# STM321.net
KiCad netlist of a schematic drawn in Altium Designer
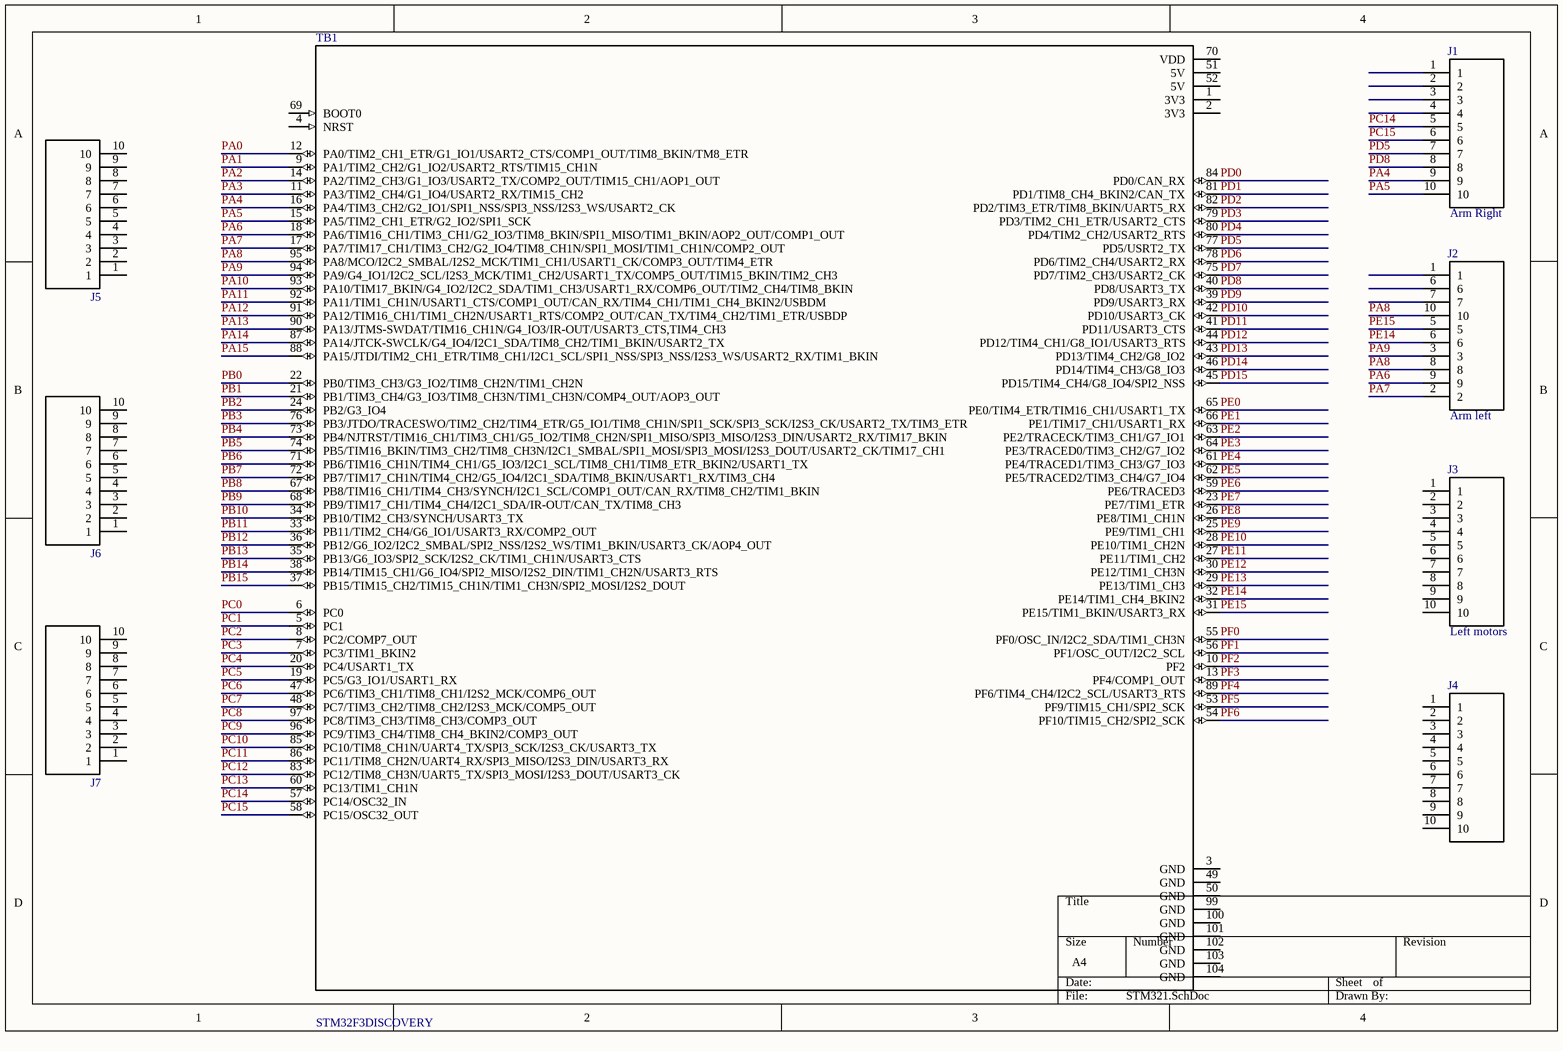
[diagram p0: STM321.SchDoc]

(export (version "E")
  (design (tool "Eeschema 10.0.6"))
  (components
    (comp (ref "J1")
      (value "2-1761603-3")
      (footprint "*TE_2-1761603-3")
      (description "Header, Pin, Idc, Amp-Latch, 10 Pos, Low Profile, Pcb, Vertical, Blue")
      (fields (field (name "MF") "TE Connectivity"))
      (libsource (lib "2-1761603-3") (part "2-1761603-3"))
    )
    (comp (ref "J2")
      (value "2-1761603-3")
      (footprint "*TE_2-1761603-3")
      (description "Header, Pin, Idc, Amp-Latch, 10 Pos, Low Profile, Pcb, Vertical, Blue")
      (fields (field (name "MF") "TE Connectivity"))
      (libsource (lib "") (part "2-1761603-3_1"))
    )
    (comp (ref "J3")
      (value "2-1761603-3")
      (footprint "*TE_2-1761603-3")
      (description "Header, Pin, Idc, Amp-Latch, 10 Pos, Low Profile, Pcb, Vertical, Blue")
      (fields (field (name "MF") "TE Connectivity"))
      (libsource (lib "2-1761603-3") (part "2-1761603-3"))
    )
    (comp (ref "J4")
      (value "2-1761603-3")
      (footprint "*TE_2-1761603-3")
      (description "Header, Pin, Idc, Amp-Latch, 10 Pos, Low Profile, Pcb, Vertical, Blue")
      (fields (field (name "MF") "TE Connectivity"))
      (libsource (lib "2-1761603-3") (part "2-1761603-3"))
    )
    (comp (ref "J5")
      (value "2-1761603-3")
      (footprint "*TE_2-1761603-3")
      (description "Header, Pin, Idc, Amp-Latch, 10 Pos, Low Profile, Pcb, Vertical, Blue")
      (fields (field (name "MF") "TE Connectivity"))
      (libsource (lib "2-1761603-3") (part "2-1761603-3"))
    )
    (comp (ref "J6")
      (value "2-1761603-3")
      (footprint "*TE_2-1761603-3")
      (description "Header, Pin, Idc, Amp-Latch, 10 Pos, Low Profile, Pcb, Vertical, Blue")
      (fields (field (name "MF") "TE Connectivity"))
      (libsource (lib "2-1761603-3") (part "2-1761603-3"))
    )
    (comp (ref "J7")
      (value "2-1761603-3")
      (footprint "*TE_2-1761603-3")
      (description "Header, Pin, Idc, Amp-Latch, 10 Pos, Low Profile, Pcb, Vertical, Blue")
      (fields (field (name "MF") "TE Connectivity"))
      (libsource (lib "2-1761603-3") (part "2-1761603-3"))
    )
    (comp (ref "TB1")
      (value "STM32F3DISCOVERY")
      (footprint "*SHIELD_STM32F3DISCOVERY")
      (description "STM32F303VCT6 Discovery STM32F3 ARMÂ® CortexÂ®-M4 MCU 32-Bit Embedded Evaluation Board")
      (fields (field (name "MF") "STMicroelectronics"))
      (libsource (lib "STM32F3DISCOVERY") (part "STM32F3DISCOVERY"))
    )
  )
  (nets
    (net (code "1") (name "/PA0") (class "Default")
      (node (ref "TB1") (pin "12") (pinfunction "PA0/TIM2_CH1_ETR/G1_IO1/USART2_CTS/COMP1_OUT/TIM8_BKIN/TM8_ETR_12") (pintype "bidirectional"))
    )
    (net (code "2") (name "/PA1") (class "Default")
      (node (ref "TB1") (pin "9") (pinfunction "PA1/TIM2_CH2/G1_IO2/USART2_RTS/TIM15_CH1N_9") (pintype "bidirectional"))
    )
    (net (code "3") (name "/PA2") (class "Default")
      (node (ref "TB1") (pin "14") (pinfunction "PA2/TIM2_CH3/G1_IO3/USART2_TX/COMP2_OUT/TIM15_CH1/AOP1_OUT_14") (pintype "bidirectional"))
    )
    (net (code "4") (name "/PA3") (class "Default")
      (node (ref "TB1") (pin "11") (pinfunction "PA3/TIM2_CH4/G1_IO4/USART2_RX/TIM15_CH2_11") (pintype "bidirectional"))
    )
    (net (code "5") (name "/PA4") (class "Default")
      (node (ref "J1") (pin "9") (pinfunction "9_9") (pintype "passive"))
      (node (ref "TB1") (pin "16") (pinfunction "PA4/TIM3_CH2/G2_IO1/SPI1_NSS/SPI3_NSS/I2S3_WS/USART2_CK_16") (pintype "bidirectional"))
    )
    (net (code "6") (name "/PA5") (class "Default")
      (node (ref "J1") (pin "10") (pinfunction "10_10") (pintype "passive"))
      (node (ref "TB1") (pin "15") (pinfunction "PA5/TIM2_CH1_ETR/G2_IO2/SPI1_SCK_15") (pintype "bidirectional"))
    )
    (net (code "7") (name "/PA6") (class "Default")
      (node (ref "J2") (pin "9") (pinfunction "9_9") (pintype "passive"))
      (node (ref "TB1") (pin "18") (pinfunction "PA6/TIM16_CH1/TIM3_CH1/G2_IO3/TIM8_BKIN/SPI1_MISO/TIM1_BKIN/AOP2_OUT/COMP1_OUT_18") (pintype "bidirectional"))
    )
    (net (code "8") (name "/PA7") (class "Default")
      (node (ref "J2") (pin "2") (pinfunction "2_2") (pintype "passive"))
      (node (ref "TB1") (pin "17") (pinfunction "PA7/TIM17_CH1/TIM3_CH2/G2_IO4/TIM8_CH1N/SPI1_MOSI/TIM1_CH1N/COMP2_OUT_17") (pintype "bidirectional"))
    )
    (net (code "9") (name "/PA8") (class "Default")
      (node (ref "J2") (pin "10") (pinfunction "10_10") (pintype "passive"))
      (node (ref "J2") (pin "8") (pinfunction "8_8") (pintype "passive"))
      (node (ref "TB1") (pin "95") (pinfunction "PA8/MCO/I2C2_SMBAL/I2S2_MCK/TIM1_CH1/USART1_CK/COMP3_OUT/TIM4_ETR_95") (pintype "bidirectional"))
    )
    (net (code "10") (name "/PA9") (class "Default")
      (node (ref "J2") (pin "3") (pinfunction "3_3") (pintype "passive"))
      (node (ref "TB1") (pin "94") (pinfunction "PA9/G4_IO1/I2C2_SCL/I2S3_MCK/TIM1_CH2/USART1_TX/COMP5_OUT/TIM15_BKIN/TIM2_CH3_94") (pintype "bidirectional"))
    )
    (net (code "11") (name "/PA10") (class "Default")
      (node (ref "TB1") (pin "93") (pinfunction "PA10/TIM17_BKIN/G4_IO2/I2C2_SDA/TIM1_CH3/USART1_RX/COMP6_OUT/TIM2_CH4/TIM8_BKIN_93") (pintype "bidirectional"))
    )
    (net (code "12") (name "/PA11") (class "Default")
      (node (ref "TB1") (pin "92") (pinfunction "PA11/TIM1_CH1N/USART1_CTS/COMP1_OUT/CAN_RX/TIM4_CH1/TIM1_CH4_BKIN2/USBDM_92") (pintype "bidirectional"))
    )
    (net (code "13") (name "/PA12") (class "Default")
      (node (ref "TB1") (pin "91") (pinfunction "PA12/TIM16_CH1/TIM1_CH2N/USART1_RTS/COMP2_OUT/CAN_TX/TIM4_CH2/TIM1_ETR/USBDP_91") (pintype "bidirectional"))
    )
    (net (code "14") (name "/PA13") (class "Default")
      (node (ref "TB1") (pin "90") (pinfunction "PA13/JTMS-SWDAT/TIM16_CH1N/G4_IO3/IR-OUT/USART3_CTS,TIM4_CH3_90") (pintype "bidirectional"))
    )
    (net (code "15") (name "/PA14") (class "Default")
      (node (ref "TB1") (pin "87") (pinfunction "PA14/JTCK-SWCLK/G4_IO4/I2C1_SDA/TIM8_CH2/TIM1_BKIN/USART2_TX_87") (pintype "bidirectional"))
    )
    (net (code "16") (name "/PA15") (class "Default")
      (node (ref "TB1") (pin "88") (pinfunction "PA15/JTDI/TIM2_CH1_ETR/TIM8_CH1/I2C1_SCL/SPI1_NSS/SPI3_NSS/I2S3_WS/USART2_RX/TIM1_BKIN_88") (pintype "bidirectional"))
    )
    (net (code "17") (name "/PB0") (class "Default")
      (node (ref "TB1") (pin "22") (pinfunction "PB0/TIM3_CH3/G3_IO2/TIM8_CH2N/TIM1_CH2N_22") (pintype "bidirectional"))
    )
    (net (code "18") (name "/PB1") (class "Default")
      (node (ref "TB1") (pin "21") (pinfunction "PB1/TIM3_CH4/G3_IO3/TIM8_CH3N/TIM1_CH3N/COMP4_OUT/AOP3_OUT_21") (pintype "bidirectional"))
    )
    (net (code "19") (name "/PB2") (class "Default")
      (node (ref "TB1") (pin "24") (pinfunction "PB2/G3_IO4_24") (pintype "bidirectional"))
    )
    (net (code "20") (name "/PB3") (class "Default")
      (node (ref "TB1") (pin "76") (pinfunction "PB3/JTDO/TRACESWO/TIM2_CH2/TIM4_ETR/G5_IO1/TIM8_CH1N/SPI1_SCK/SPI3_SCK/I2S3_CK/USART2_TX/TIM3_ETR_76") (pintype "bidirectional"))
    )
    (net (code "21") (name "/PB4") (class "Default")
      (node (ref "TB1") (pin "73") (pinfunction "PB4/NJTRST/TIM16_CH1/TIM3_CH1/G5_IO2/TIM8_CH2N/SPI1_MISO/SPI3_MISO/I2S3_DIN/USART2_RX/TIM17_BKIN_73") (pintype "bidirectional"))
    )
    (net (code "22") (name "/PB5") (class "Default")
      (node (ref "TB1") (pin "74") (pinfunction "PB5/TIM16_BKIN/TIM3_CH2/TIM8_CH3N/I2C1_SMBAL/SPI1_MOSI/SPI3_MOSI/I2S3_DOUT/USART2_CK/TIM17_CH1_74") (pintype "bidirectional"))
    )
    (net (code "23") (name "/PB6") (class "Default")
      (node (ref "TB1") (pin "71") (pinfunction "PB6/TIM16_CH1N/TIM4_CH1/G5_IO3/I2C1_SCL/TIM8_CH1/TIM8_ETR_BKIN2/USART1_TX_71") (pintype "bidirectional"))
    )
    (net (code "24") (name "/PB7") (class "Default")
      (node (ref "TB1") (pin "72") (pinfunction "PB7/TIM17_CH1N/TIM4_CH2/G5_IO4/I2C1_SDA/TIM8_BKIN/USART1_RX/TIM3_CH4_72") (pintype "bidirectional"))
    )
    (net (code "25") (name "/PB8") (class "Default")
      (node (ref "TB1") (pin "67") (pinfunction "PB8/TIM16_CH1/TIM4_CH3/SYNCH/I2C1_SCL/COMP1_OUT/CAN_RX/TIM8_CH2/TIM1_BKIN_67") (pintype "bidirectional"))
    )
    (net (code "26") (name "/PB9") (class "Default")
      (node (ref "TB1") (pin "68") (pinfunction "PB9/TIM17_CH1/TIM4_CH4/I2C1_SDA/IR-OUT/CAN_TX/TIM8_CH3_68") (pintype "bidirectional"))
    )
    (net (code "27") (name "/PB10") (class "Default")
      (node (ref "TB1") (pin "34") (pinfunction "PB10/TIM2_CH3/SYNCH/USART3_TX_34") (pintype "bidirectional"))
    )
    (net (code "28") (name "/PB11") (class "Default")
      (node (ref "TB1") (pin "33") (pinfunction "PB11/TIM2_CH4/G6_IO1/USART3_RX/COMP2_OUT_33") (pintype "bidirectional"))
    )
    (net (code "29") (name "/PB12") (class "Default")
      (node (ref "TB1") (pin "36") (pinfunction "PB12/G6_IO2/I2C2_SMBAL/SPI2_NSS/I2S2_WS/TIM1_BKIN/USART3_CK/AOP4_OUT_36") (pintype "bidirectional"))
    )
    (net (code "30") (name "/PB13") (class "Default")
      (node (ref "TB1") (pin "35") (pinfunction "PB13/G6_IO3/SPI2_SCK/I2S2_CK/TIM1_CH1N/USART3_CTS_35") (pintype "bidirectional"))
    )
    (net (code "31") (name "/PB14") (class "Default")
      (node (ref "TB1") (pin "38") (pinfunction "PB14/TIM15_CH1/G6_IO4/SPI2_MISO/I2S2_DIN/TIM1_CH2N/USART3_RTS_38") (pintype "bidirectional"))
    )
    (net (code "32") (name "/PB15") (class "Default")
      (node (ref "TB1") (pin "37") (pinfunction "PB15/TIM15_CH2/TIM15_CH1N/TIM1_CH3N/SPI2_MOSI/I2S2_DOUT_37") (pintype "bidirectional"))
    )
    (net (code "33") (name "/PC0") (class "Default")
      (node (ref "TB1") (pin "6") (pinfunction "PC0_6") (pintype "bidirectional"))
    )
    (net (code "34") (name "/PC1") (class "Default")
      (node (ref "TB1") (pin "5") (pinfunction "PC1_5") (pintype "bidirectional"))
    )
    (net (code "35") (name "/PC2") (class "Default")
      (node (ref "TB1") (pin "8") (pinfunction "PC2/COMP7_OUT_8") (pintype "bidirectional"))
    )
    (net (code "36") (name "/PC3") (class "Default")
      (node (ref "TB1") (pin "7") (pinfunction "PC3/TIM1_BKIN2_7") (pintype "bidirectional"))
    )
    (net (code "37") (name "/PC4") (class "Default")
      (node (ref "TB1") (pin "20") (pinfunction "PC4/USART1_TX_20") (pintype "bidirectional"))
    )
    (net (code "38") (name "/PC5") (class "Default")
      (node (ref "TB1") (pin "19") (pinfunction "PC5/G3_IO1/USART1_RX_19") (pintype "bidirectional"))
    )
    (net (code "39") (name "/PC6") (class "Default")
      (node (ref "TB1") (pin "47") (pinfunction "PC6/TIM3_CH1/TIM8_CH1/I2S2_MCK/COMP6_OUT_47") (pintype "bidirectional"))
    )
    (net (code "40") (name "/PC7") (class "Default")
      (node (ref "TB1") (pin "48") (pinfunction "PC7/TIM3_CH2/TIM8_CH2/I2S3_MCK/COMP5_OUT_48") (pintype "bidirectional"))
    )
    (net (code "41") (name "/PC8") (class "Default")
      (node (ref "TB1") (pin "97") (pinfunction "PC8/TIM3_CH3/TIM8_CH3/COMP3_OUT_97") (pintype "bidirectional"))
    )
    (net (code "42") (name "/PC9") (class "Default")
      (node (ref "TB1") (pin "96") (pinfunction "PC9/TIM3_CH4/TIM8_CH4_BKIN2/COMP3_OUT_96") (pintype "bidirectional"))
    )
    (net (code "43") (name "/PC10") (class "Default")
      (node (ref "TB1") (pin "85") (pinfunction "PC10/TIM8_CH1N/UART4_TX/SPI3_SCK/I2S3_CK/USART3_TX_85") (pintype "bidirectional"))
    )
    (net (code "44") (name "/PC11") (class "Default")
      (node (ref "TB1") (pin "86") (pinfunction "PC11/TIM8_CH2N/UART4_RX/SPI3_MISO/I2S3_DIN/USART3_RX_86") (pintype "bidirectional"))
    )
    (net (code "45") (name "/PC12") (class "Default")
      (node (ref "TB1") (pin "83") (pinfunction "PC12/TIM8_CH3N/UART5_TX/SPI3_MOSI/I2S3_DOUT/USART3_CK_83") (pintype "bidirectional"))
    )
    (net (code "46") (name "/PC13") (class "Default")
      (node (ref "TB1") (pin "60") (pinfunction "PC13/TIM1_CH1N_60") (pintype "bidirectional"))
    )
    (net (code "47") (name "/PC14") (class "Default")
      (node (ref "J1") (pin "5") (pinfunction "5_5") (pintype "passive"))
      (node (ref "TB1") (pin "57") (pinfunction "PC14/OSC32_IN_57") (pintype "bidirectional"))
    )
    (net (code "48") (name "/PC15") (class "Default")
      (node (ref "J1") (pin "6") (pinfunction "6_6") (pintype "passive"))
      (node (ref "TB1") (pin "58") (pinfunction "PC15/OSC32_OUT_58") (pintype "bidirectional"))
    )
    (net (code "49") (name "/PD0") (class "Default")
      (node (ref "TB1") (pin "84") (pinfunction "PD0/CAN_RX_84") (pintype "bidirectional"))
    )
    (net (code "50") (name "/PD1") (class "Default")
      (node (ref "TB1") (pin "81") (pinfunction "PD1/TIM8_CH4_BKIN2/CAN_TX_81") (pintype "bidirectional"))
    )
    (net (code "51") (name "/PD2") (class "Default")
      (node (ref "TB1") (pin "82") (pinfunction "PD2/TIM3_ETR/TIM8_BKIN/UART5_RX_82") (pintype "bidirectional"))
    )
    (net (code "52") (name "/PD3") (class "Default")
      (node (ref "TB1") (pin "79") (pinfunction "PD3/TIM2_CH1_ETR/USART2_CTS_79") (pintype "bidirectional"))
    )
    (net (code "53") (name "/PD4") (class "Default")
      (node (ref "TB1") (pin "80") (pinfunction "PD4/TIM2_CH2/USART2_RTS_80") (pintype "bidirectional"))
    )
    (net (code "54") (name "/PD5") (class "Default")
      (node (ref "J1") (pin "7") (pinfunction "7_7") (pintype "passive"))
      (node (ref "TB1") (pin "77") (pinfunction "PD5/USRT2_TX_77") (pintype "bidirectional"))
    )
    (net (code "55") (name "/PD6") (class "Default")
      (node (ref "TB1") (pin "78") (pinfunction "PD6/TIM2_CH4/USART2_RX_78") (pintype "bidirectional"))
    )
    (net (code "56") (name "/PD7") (class "Default")
      (node (ref "TB1") (pin "75") (pinfunction "PD7/TIM2_CH3/USART2_CK_75") (pintype "bidirectional"))
    )
    (net (code "57") (name "/PD8") (class "Default")
      (node (ref "J1") (pin "8") (pinfunction "8_8") (pintype "passive"))
      (node (ref "TB1") (pin "40") (pinfunction "PD8/USART3_TX_40") (pintype "bidirectional"))
    )
    (net (code "58") (name "/PD9") (class "Default")
      (node (ref "TB1") (pin "39") (pinfunction "PD9/USART3_RX_39") (pintype "bidirectional"))
    )
    (net (code "59") (name "/PD10") (class "Default")
      (node (ref "TB1") (pin "42") (pinfunction "PD10/USART3_CK_42") (pintype "bidirectional"))
    )
    (net (code "60") (name "/PD11") (class "Default")
      (node (ref "TB1") (pin "41") (pinfunction "PD11/USART3_CTS_41") (pintype "bidirectional"))
    )
    (net (code "61") (name "/PD12") (class "Default")
      (node (ref "TB1") (pin "44") (pinfunction "PD12/TIM4_CH1/G8_IO1/USART3_RTS_44") (pintype "bidirectional"))
    )
    (net (code "62") (name "/PD13") (class "Default")
      (node (ref "TB1") (pin "43") (pinfunction "PD13/TIM4_CH2/G8_IO2_43") (pintype "bidirectional"))
    )
    (net (code "63") (name "/PD14") (class "Default")
      (node (ref "TB1") (pin "46") (pinfunction "PD14/TIM4_CH3/G8_IO3_46") (pintype "bidirectional"))
    )
    (net (code "64") (name "/PD15") (class "Default")
      (node (ref "TB1") (pin "45") (pinfunction "PD15/TIM4_CH4/G8_IO4/SPI2_NSS_45") (pintype "bidirectional"))
    )
    (net (code "65") (name "/PE0") (class "Default")
      (node (ref "TB1") (pin "65") (pinfunction "PE0/TIM4_ETR/TIM16_CH1/USART1_TX_65") (pintype "bidirectional"))
    )
    (net (code "66") (name "/PE1") (class "Default")
      (node (ref "TB1") (pin "66") (pinfunction "PE1/TIM17_CH1/USART1_RX_66") (pintype "bidirectional"))
    )
    (net (code "67") (name "/PE2") (class "Default")
      (node (ref "TB1") (pin "63") (pinfunction "PE2/TRACECK/TIM3_CH1/G7_IO1_63") (pintype "bidirectional"))
    )
    (net (code "68") (name "/PE3") (class "Default")
      (node (ref "TB1") (pin "64") (pinfunction "PE3/TRACED0/TIM3_CH2/G7_IO2_64") (pintype "bidirectional"))
    )
    (net (code "69") (name "/PE4") (class "Default")
      (node (ref "TB1") (pin "61") (pinfunction "PE4/TRACED1/TIM3_CH3/G7_IO3_61") (pintype "bidirectional"))
    )
    (net (code "70") (name "/PE5") (class "Default")
      (node (ref "TB1") (pin "62") (pinfunction "PE5/TRACED2/TIM3_CH4/G7_IO4_62") (pintype "bidirectional"))
    )
    (net (code "71") (name "/PE6") (class "Default")
      (node (ref "TB1") (pin "59") (pinfunction "PE6/TRACED3_59") (pintype "bidirectional"))
    )
    (net (code "72") (name "/PE7") (class "Default")
      (node (ref "TB1") (pin "23") (pinfunction "PE7/TIM1_ETR_23") (pintype "bidirectional"))
    )
    (net (code "73") (name "/PE8") (class "Default")
      (node (ref "TB1") (pin "26") (pinfunction "PE8/TIM1_CH1N_26") (pintype "bidirectional"))
    )
    (net (code "74") (name "/PE9") (class "Default")
      (node (ref "TB1") (pin "25") (pinfunction "PE9/TIM1_CH1_25") (pintype "bidirectional"))
    )
    (net (code "75") (name "/PE10") (class "Default")
      (node (ref "TB1") (pin "28") (pinfunction "PE10/TIM1_CH2N_28") (pintype "bidirectional"))
    )
    (net (code "76") (name "/PE11") (class "Default")
      (node (ref "TB1") (pin "27") (pinfunction "PE11/TIM1_CH2_27") (pintype "bidirectional"))
    )
    (net (code "77") (name "/PE12") (class "Default")
      (node (ref "TB1") (pin "30") (pinfunction "PE12/TIM1_CH3N_30") (pintype "bidirectional"))
    )
    (net (code "78") (name "/PE13") (class "Default")
      (node (ref "TB1") (pin "29") (pinfunction "PE13/TIM1_CH3_29") (pintype "bidirectional"))
    )
    (net (code "79") (name "/PE14") (class "Default")
      (node (ref "J2") (pin "6") (pinfunction "6_6") (pintype "passive"))
      (node (ref "TB1") (pin "32") (pinfunction "PE14/TIM1_CH4_BKIN2_32") (pintype "bidirectional"))
    )
    (net (code "80") (name "/PE15") (class "Default")
      (node (ref "J2") (pin "5") (pinfunction "5_5") (pintype "passive"))
      (node (ref "TB1") (pin "31") (pinfunction "PE15/TIM1_BKIN/USART3_RX_31") (pintype "bidirectional"))
    )
    (net (code "81") (name "/PF0") (class "Default")
      (node (ref "TB1") (pin "55") (pinfunction "PF0/OSC_IN/I2C2_SDA/TIM1_CH3N_55") (pintype "bidirectional"))
    )
    (net (code "82") (name "/PF1") (class "Default")
      (node (ref "TB1") (pin "56") (pinfunction "PF1/OSC_OUT/I2C2_SCL_56") (pintype "bidirectional"))
    )
    (net (code "83") (name "/PF2") (class "Default")
      (node (ref "TB1") (pin "10") (pinfunction "PF2_10") (pintype "bidirectional"))
    )
    (net (code "84") (name "/PF3") (class "Default")
      (node (ref "TB1") (pin "13") (pinfunction "PF4/COMP1_OUT_13") (pintype "bidirectional"))
    )
    (net (code "85") (name "/PF4") (class "Default")
      (node (ref "TB1") (pin "89") (pinfunction "PF6/TIM4_CH4/I2C2_SCL/USART3_RTS_89") (pintype "bidirectional"))
    )
    (net (code "86") (name "/PF5") (class "Default")
      (node (ref "TB1") (pin "53") (pinfunction "PF9/TIM15_CH1/SPI2_SCK_53") (pintype "bidirectional"))
    )
    (net (code "87") (name "/PF6") (class "Default")
      (node (ref "TB1") (pin "54") (pinfunction "PF10/TIM15_CH2/SPI2_SCK_54") (pintype "bidirectional"))
    )
    (net (code "88") (name "unconnected-(J1-Pad1)") (class "Default")
      (node (ref "J1") (pin "1") (pinfunction "1_1") (pintype "passive"))
    )
    (net (code "89") (name "unconnected-(J1-Pad2)") (class "Default")
      (node (ref "J1") (pin "2") (pinfunction "2_2") (pintype "passive"))
    )
    (net (code "90") (name "unconnected-(J1-Pad3)") (class "Default")
      (node (ref "J1") (pin "3") (pinfunction "3_3") (pintype "passive"))
    )
    (net (code "91") (name "unconnected-(J1-Pad4)") (class "Default")
      (node (ref "J1") (pin "4") (pinfunction "4_4") (pintype "passive"))
    )
    (net (code "92") (name "unconnected-(J2-Pad1)") (class "Default")
      (node (ref "J2") (pin "1") (pinfunction "1_1") (pintype "passive"))
    )
    (net (code "93") (name "unconnected-(J2-Pad6)") (class "Default")
      (node (ref "J2") (pin "6") (pinfunction "6_6") (pintype "passive"))
    )
    (net (code "94") (name "unconnected-(J2-Pad7)") (class "Default")
      (node (ref "J2") (pin "7") (pinfunction "7_7") (pintype "passive"))
    )
    (net (code "95") (name "unconnected-(J3-Pad1)") (class "Default")
      (node (ref "J3") (pin "1") (pinfunction "1_1") (pintype "passive"))
    )
    (net (code "96") (name "unconnected-(J3-Pad2)") (class "Default")
      (node (ref "J3") (pin "2") (pinfunction "2_2") (pintype "passive"))
    )
    (net (code "97") (name "unconnected-(J3-Pad3)") (class "Default")
      (node (ref "J3") (pin "3") (pinfunction "3_3") (pintype "passive"))
    )
    (net (code "98") (name "unconnected-(J3-Pad4)") (class "Default")
      (node (ref "J3") (pin "4") (pinfunction "4_4") (pintype "passive"))
    )
    (net (code "99") (name "unconnected-(J3-Pad5)") (class "Default")
      (node (ref "J3") (pin "5") (pinfunction "5_5") (pintype "passive"))
    )
    (net (code "100") (name "unconnected-(J3-Pad6)") (class "Default")
      (node (ref "J3") (pin "6") (pinfunction "6_6") (pintype "passive"))
    )
    (net (code "101") (name "unconnected-(J3-Pad7)") (class "Default")
      (node (ref "J3") (pin "7") (pinfunction "7_7") (pintype "passive"))
    )
    (net (code "102") (name "unconnected-(J3-Pad8)") (class "Default")
      (node (ref "J3") (pin "8") (pinfunction "8_8") (pintype "passive"))
    )
    (net (code "103") (name "unconnected-(J3-Pad9)") (class "Default")
      (node (ref "J3") (pin "9") (pinfunction "9_9") (pintype "passive"))
    )
    (net (code "104") (name "unconnected-(J3-Pad10)") (class "Default")
      (node (ref "J3") (pin "10") (pinfunction "10_10") (pintype "passive"))
    )
    (net (code "105") (name "unconnected-(J4-Pad1)") (class "Default")
      (node (ref "J4") (pin "1") (pinfunction "1_1") (pintype "passive"))
    )
    (net (code "106") (name "unconnected-(J4-Pad2)") (class "Default")
      (node (ref "J4") (pin "2") (pinfunction "2_2") (pintype "passive"))
    )
    (net (code "107") (name "unconnected-(J4-Pad3)") (class "Default")
      (node (ref "J4") (pin "3") (pinfunction "3_3") (pintype "passive"))
    )
    (net (code "108") (name "unconnected-(J4-Pad4)") (class "Default")
      (node (ref "J4") (pin "4") (pinfunction "4_4") (pintype "passive"))
    )
    (net (code "109") (name "unconnected-(J4-Pad5)") (class "Default")
      (node (ref "J4") (pin "5") (pinfunction "5_5") (pintype "passive"))
    )
    (net (code "110") (name "unconnected-(J4-Pad6)") (class "Default")
      (node (ref "J4") (pin "6") (pinfunction "6_6") (pintype "passive"))
    )
    (net (code "111") (name "unconnected-(J4-Pad7)") (class "Default")
      (node (ref "J4") (pin "7") (pinfunction "7_7") (pintype "passive"))
    )
    (net (code "112") (name "unconnected-(J4-Pad8)") (class "Default")
      (node (ref "J4") (pin "8") (pinfunction "8_8") (pintype "passive"))
    )
    (net (code "113") (name "unconnected-(J4-Pad9)") (class "Default")
      (node (ref "J4") (pin "9") (pinfunction "9_9") (pintype "passive"))
    )
    (net (code "114") (name "unconnected-(J4-Pad10)") (class "Default")
      (node (ref "J4") (pin "10") (pinfunction "10_10") (pintype "passive"))
    )
    (net (code "115") (name "unconnected-(J5-Pad1)") (class "Default")
      (node (ref "J5") (pin "1") (pinfunction "1_1") (pintype "passive"))
    )
    (net (code "116") (name "unconnected-(J5-Pad2)") (class "Default")
      (node (ref "J5") (pin "2") (pinfunction "2_2") (pintype "passive"))
    )
    (net (code "117") (name "unconnected-(J5-Pad3)") (class "Default")
      (node (ref "J5") (pin "3") (pinfunction "3_3") (pintype "passive"))
    )
    (net (code "118") (name "unconnected-(J5-Pad4)") (class "Default")
      (node (ref "J5") (pin "4") (pinfunction "4_4") (pintype "passive"))
    )
    (net (code "119") (name "unconnected-(J5-Pad5)") (class "Default")
      (node (ref "J5") (pin "5") (pinfunction "5_5") (pintype "passive"))
    )
    (net (code "120") (name "unconnected-(J5-Pad6)") (class "Default")
      (node (ref "J5") (pin "6") (pinfunction "6_6") (pintype "passive"))
    )
    (net (code "121") (name "unconnected-(J5-Pad7)") (class "Default")
      (node (ref "J5") (pin "7") (pinfunction "7_7") (pintype "passive"))
    )
    (net (code "122") (name "unconnected-(J5-Pad8)") (class "Default")
      (node (ref "J5") (pin "8") (pinfunction "8_8") (pintype "passive"))
    )
    (net (code "123") (name "unconnected-(J5-Pad9)") (class "Default")
      (node (ref "J5") (pin "9") (pinfunction "9_9") (pintype "passive"))
    )
    (net (code "124") (name "unconnected-(J5-Pad10)") (class "Default")
      (node (ref "J5") (pin "10") (pinfunction "10_10") (pintype "passive"))
    )
    (net (code "125") (name "unconnected-(J6-Pad1)") (class "Default")
      (node (ref "J6") (pin "1") (pinfunction "1_1") (pintype "passive"))
    )
    (net (code "126") (name "unconnected-(J6-Pad2)") (class "Default")
      (node (ref "J6") (pin "2") (pinfunction "2_2") (pintype "passive"))
    )
    (net (code "127") (name "unconnected-(J6-Pad3)") (class "Default")
      (node (ref "J6") (pin "3") (pinfunction "3_3") (pintype "passive"))
    )
    (net (code "128") (name "unconnected-(J6-Pad4)") (class "Default")
      (node (ref "J6") (pin "4") (pinfunction "4_4") (pintype "passive"))
    )
    (net (code "129") (name "unconnected-(J6-Pad5)") (class "Default")
      (node (ref "J6") (pin "5") (pinfunction "5_5") (pintype "passive"))
    )
    (net (code "130") (name "unconnected-(J6-Pad6)") (class "Default")
      (node (ref "J6") (pin "6") (pinfunction "6_6") (pintype "passive"))
    )
    (net (code "131") (name "unconnected-(J6-Pad7)") (class "Default")
      (node (ref "J6") (pin "7") (pinfunction "7_7") (pintype "passive"))
    )
    (net (code "132") (name "unconnected-(J6-Pad8)") (class "Default")
      (node (ref "J6") (pin "8") (pinfunction "8_8") (pintype "passive"))
    )
    (net (code "133") (name "unconnected-(J6-Pad9)") (class "Default")
      (node (ref "J6") (pin "9") (pinfunction "9_9") (pintype "passive"))
    )
    (net (code "134") (name "unconnected-(J6-Pad10)") (class "Default")
      (node (ref "J6") (pin "10") (pinfunction "10_10") (pintype "passive"))
    )
    (net (code "135") (name "unconnected-(J7-Pad1)") (class "Default")
      (node (ref "J7") (pin "1") (pinfunction "1_1") (pintype "passive"))
    )
    (net (code "136") (name "unconnected-(J7-Pad2)") (class "Default")
      (node (ref "J7") (pin "2") (pinfunction "2_2") (pintype "passive"))
    )
    (net (code "137") (name "unconnected-(J7-Pad3)") (class "Default")
      (node (ref "J7") (pin "3") (pinfunction "3_3") (pintype "passive"))
    )
    (net (code "138") (name "unconnected-(J7-Pad4)") (class "Default")
      (node (ref "J7") (pin "4") (pinfunction "4_4") (pintype "passive"))
    )
    (net (code "139") (name "unconnected-(J7-Pad5)") (class "Default")
      (node (ref "J7") (pin "5") (pinfunction "5_5") (pintype "passive"))
    )
    (net (code "140") (name "unconnected-(J7-Pad6)") (class "Default")
      (node (ref "J7") (pin "6") (pinfunction "6_6") (pintype "passive"))
    )
    (net (code "141") (name "unconnected-(J7-Pad7)") (class "Default")
      (node (ref "J7") (pin "7") (pinfunction "7_7") (pintype "passive"))
    )
    (net (code "142") (name "unconnected-(J7-Pad8)") (class "Default")
      (node (ref "J7") (pin "8") (pinfunction "8_8") (pintype "passive"))
    )
    (net (code "143") (name "unconnected-(J7-Pad9)") (class "Default")
      (node (ref "J7") (pin "9") (pinfunction "9_9") (pintype "passive"))
    )
    (net (code "144") (name "unconnected-(J7-Pad10)") (class "Default")
      (node (ref "J7") (pin "10") (pinfunction "10_10") (pintype "passive"))
    )
    (net (code "145") (name "unconnected-(TB1-3V3-Pad1)") (class "Default")
      (node (ref "TB1") (pin "1") (pinfunction "3V3_1") (pintype "power_in"))
    )
    (net (code "146") (name "unconnected-(TB1-3V3-Pad2)") (class "Default")
      (node (ref "TB1") (pin "2") (pinfunction "3V3_2") (pintype "power_in"))
    )
    (net (code "147") (name "unconnected-(TB1-5V-Pad51)") (class "Default")
      (node (ref "TB1") (pin "51") (pinfunction "5V_51") (pintype "power_in"))
    )
    (net (code "148") (name "unconnected-(TB1-5V-Pad52)") (class "Default")
      (node (ref "TB1") (pin "52") (pinfunction "5V_52") (pintype "power_in"))
    )
    (net (code "149") (name "unconnected-(TB1-BOOT0-Pad69)") (class "Default")
      (node (ref "TB1") (pin "69") (pinfunction "BOOT0_69") (pintype "input"))
    )
    (net (code "150") (name "unconnected-(TB1-GND-Pad3)") (class "Default")
      (node (ref "TB1") (pin "3") (pinfunction "GND_3") (pintype "power_in"))
    )
    (net (code "151") (name "unconnected-(TB1-GND-Pad49)") (class "Default")
      (node (ref "TB1") (pin "49") (pinfunction "GND_49") (pintype "power_in"))
    )
    (net (code "152") (name "unconnected-(TB1-GND-Pad50)") (class "Default")
      (node (ref "TB1") (pin "50") (pinfunction "GND_50") (pintype "power_in"))
    )
    (net (code "153") (name "unconnected-(TB1-GND-Pad99)") (class "Default")
      (node (ref "TB1") (pin "99") (pinfunction "GND_99") (pintype "power_in"))
    )
    (net (code "154") (name "unconnected-(TB1-GND-Pad100)") (class "Default")
      (node (ref "TB1") (pin "100") (pinfunction "GND_100") (pintype "power_in"))
    )
    (net (code "155") (name "unconnected-(TB1-GND-Pad101)") (class "Default")
      (node (ref "TB1") (pin "101") (pinfunction "GND_101") (pintype "power_in"))
    )
    (net (code "156") (name "unconnected-(TB1-GND-Pad102)") (class "Default")
      (node (ref "TB1") (pin "102") (pinfunction "GND_102") (pintype "power_in"))
    )
    (net (code "157") (name "unconnected-(TB1-GND-Pad103)") (class "Default")
      (node (ref "TB1") (pin "103") (pinfunction "GND_103") (pintype "power_in"))
    )
    (net (code "158") (name "unconnected-(TB1-GND-Pad104)") (class "Default")
      (node (ref "TB1") (pin "104") (pinfunction "GND_104") (pintype "power_in"))
    )
    (net (code "159") (name "unconnected-(TB1-NRST-Pad4)") (class "Default")
      (node (ref "TB1") (pin "4") (pinfunction "NRST_4") (pintype "input"))
    )
    (net (code "160") (name "unconnected-(TB1-VDD-Pad70)") (class "Default")
      (node (ref "TB1") (pin "70") (pinfunction "VDD_70") (pintype "power_in"))
    )
  )
)
